# Sheet2.net
KiCad netlist of a schematic drawn in Altium Designer
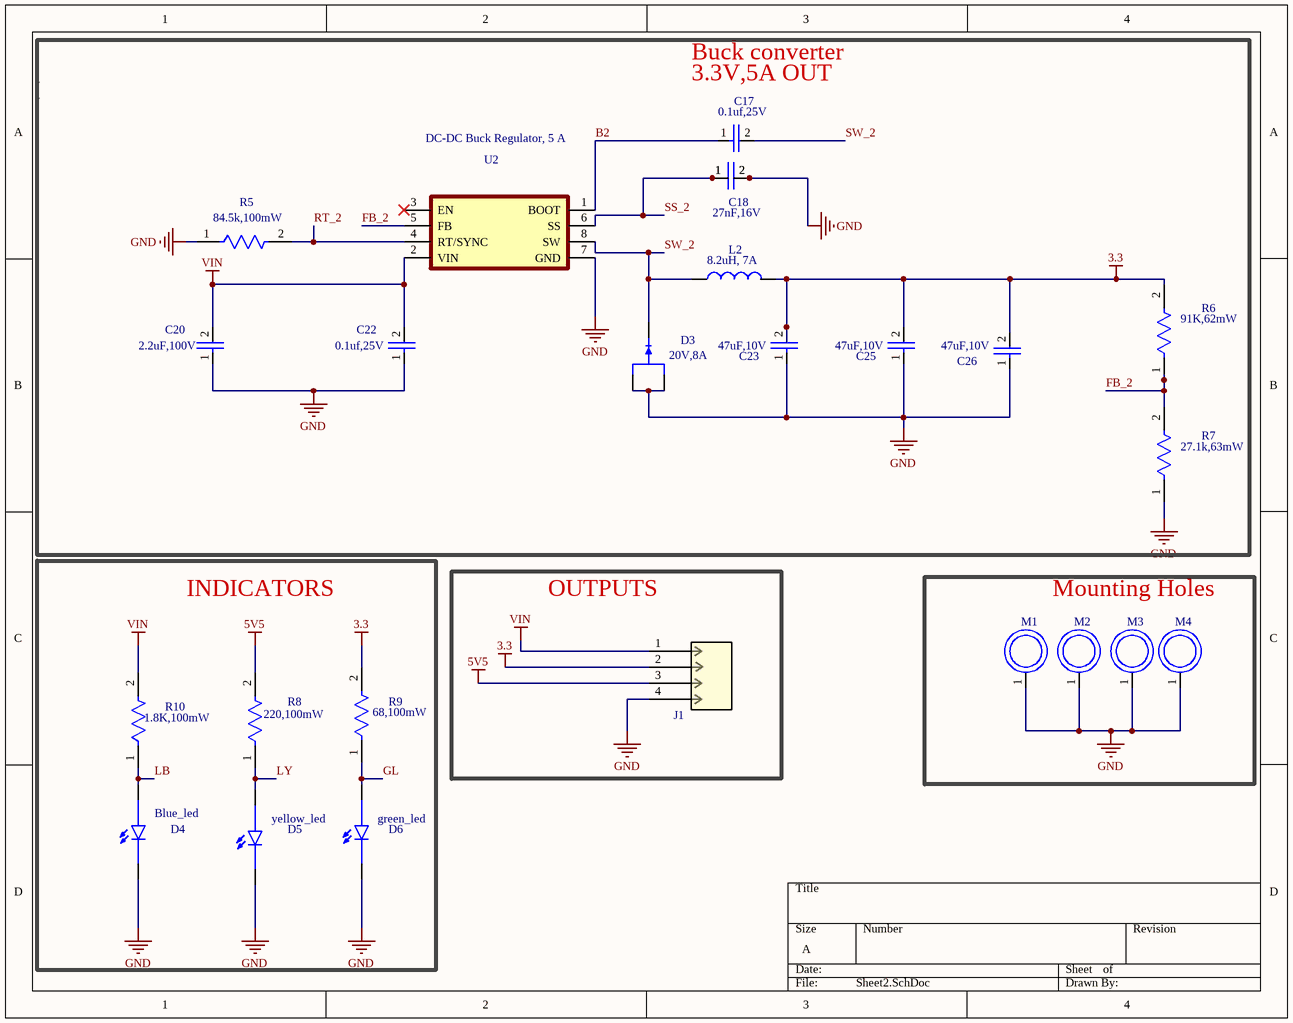
[diagram p0: Sheet2.SchDoc]

(export (version "E")
  (design (tool "Eeschema 10.0.6"))
  (components
    (comp (ref "C17")
      (value "0.1uf,25V")
      (footprint "CC0603KRX7R8BB104")
      (description "25V 100nF X7R ±10% 0603 Ceramic Capacitors ROHS")
      (fields (field (name "MANAFUCTURER PART NUMBER") "CC0603KRX7R8BB104"))
      (libsource (lib "Schlib1") (part "CC0603KRX7R8BB104"))
    )
    (comp (ref "C18")
      (value "27nF,16V")
      (footprint "C0805C273K4HACAUTO")
      (description "16V 27nF X8R ±10% 0805 Ceramic Capacitors ROHS")
      (libsource (lib "Schlib1") (part "C0805C273K4HACAUTO"))
    )
    (comp (ref "C20")
      (value "2.2uF,100V")
      (footprint "CL31A106KBHNNNE")
      (description "100V 2.2uF X7R ±10% 1206 Ceramic Capacitors ROHS")
      (fields (field (name "MANAFUCTURER PART NUMBER") "CL31B225KCHSNNE"))
      (libsource (lib "Schlib1") (part "CL31B225KCHSNNE"))
    )
    (comp (ref "C22")
      (value "0.1uf,25V")
      (footprint "CC0603KRX7R8BB104")
      (description "25V 100nF X7R ±10% 0603 Ceramic Capacitors ROHS")
      (fields (field (name "MANAFUCTURER PART NUMBER") "CC0603KRX7R8BB104"))
      (libsource (lib "Schlib1") (part "CC0603KRX7R8BB104"))
    )
    (comp (ref "C23")
      (value "47uF,10V")
      (footprint "GRM31CR61A476ME15L")
      (description "10V 47uF X5R ±20% 1206 Ceramic Capacitors ROHS")
      (fields (field (name "MANAFUCTURER PART NUMBER") "GRM31CR61A476ME15L"))
      (libsource (lib "Schlib1") (part "GRM31CR61A476ME15L"))
    )
    (comp (ref "C25")
      (value "47uF,10V")
      (footprint "GRM31CR61A476ME15L")
      (description "10V 47uF X5R ±20% 1206 Ceramic Capacitors ROHS")
      (fields (field (name "MANAFUCTURER PART NUMBER") "GRM31CR61A476ME15L"))
      (libsource (lib "Schlib1") (part "GRM31CR61A476ME15L"))
    )
    (comp (ref "C26")
      (value "47uF,10V")
      (footprint "GRM31CR61A476ME15L")
      (description "10V 47uF X5R ±20% 1206 Ceramic Capacitors ROHS")
      (fields (field (name "MANAFUCTURER PART NUMBER") "GRM31CR61A476ME15L"))
      (libsource (lib "Schlib1") (part "GRM31CR61A476ME15L"))
    )
    (comp (ref "D3")
      (value "20V,8A")
      (footprint "SS12P2L-M3/86A")
      (description "20V 560mV@12A 12A TO-277A Single Diodes ROHS")
      (fields (field (name "MANAFUCTURER PART NUMBER") "SS12P2L-M3/86A"))
      (libsource (lib "Schlib1") (part "SS12P2L-M3/86A"))
    )
    (comp (ref "D4")
      (value "Blue_led")
      (footprint "XL-1608UBC-04")
      (description "20mA 3.3V Blue 70mW 0603 LED Indication - Discrete ROHS")
      (fields (field (name "MANAFUCTURER PART NUMBER") "XL-1608UBC-04"))
      (libsource (lib "Schlib1") (part "XL-1608UBC-04"))
    )
    (comp (ref "D5")
      (value "yellow_led")
      (footprint "XL-1608UWC-04")
      (description "20mA 13700K~33000K White 2.7V 70mW 0603 LED Indication - Discrete ROHS")
      (libsource (lib "Schlib1") (part "XL-1608UWC-04"))
    )
    (comp (ref "D6")
      (value "green_led")
      (footprint "LTST-C190GKT")
      (description "63mW 27.1kΩ ±25ppm/℃ Thin Film Resistor ±0.1% 0402 Chip Resistor - Surface Mount ROHS")
      (libsource (lib "Schlib1") (part "LTST-C190GKT"))
    )
    (comp (ref "J1")
      (value "Through Hole,P=2.54mm")
      (footprint "PBC04SAAN")
      (libsource (lib "Schlib1") (part "PBC04SAAN"))
    )
    (comp (ref "L2")
      (value "8.2uH, 7A")
      (footprint "SCIHP1040-8R2M")
      (description "7A 8.2uH ±20% 10A 31mΩ SMD,11.5x10.2mm Fixed Inductors ROHS")
      (fields (field (name "MANAFUCTURER PART NUMBER") "SCIHP1040-8R2M"))
      (libsource (lib "Schlib1") (part "SCIHP1040-8R2M"))
    )
    (comp (ref "M1")
      (value "2..2mm")
      (footprint "mountinh hole")
      (description "mounting hole 2.2m")
      (libsource (lib "Schlib1") (part "mountin_holes"))
    )
    (comp (ref "M2")
      (value "2..2mm")
      (footprint "mountinh hole")
      (description "mounting hole 2.2m")
      (libsource (lib "Schlib1") (part "mountin_holes"))
    )
    (comp (ref "M3")
      (value "2..2mm")
      (footprint "mountinh hole")
      (description "mounting hole 2.2m")
      (libsource (lib "Schlib1") (part "mountin_holes"))
    )
    (comp (ref "M4")
      (value "2..2mm")
      (footprint "mountinh hole")
      (description "mounting hole 2.2m")
      (libsource (lib "Schlib1") (part "mountin_holes"))
    )
    (comp (ref "R5")
      (value "84.5k,100mW")
      (footprint "RC0603FR-0784K5L")
      (description "100mW 84.5kΩ 75V ±100ppm/℃ Thick Film Resistor ±1% 0603 Chip Resistor - Surface Mount ROHS")
      (fields (field (name "MANAFUCTURER PART NUMBER") "RC0603FR-0784K5L"))
      (libsource (lib "Schlib1") (part "RC0603FR-0784K5L"))
    )
    (comp (ref "R6")
      (value "91K,62mW")
      (footprint "RC0402FR-0791KL")
      (description "91kΩ 62.5mW 50V ±100ppm/℃ Thick Film Resistor ±1% 0402 Chip Resistor - Surface Mount ROHS")
      (libsource (lib "Schlib1") (part "RC0402FR-0791KL"))
    )
    (comp (ref "R7")
      (value "27.1k,63mW")
      (footprint "TNPW040227K1BEED")
      (description "63mW 27.1kΩ ±25ppm/℃ Thin Film Resistor ±0.1% 0402 Chip Resistor - Surface Mount ROHS")
      (libsource (lib "Schlib1") (part "TNPW040227K1BEED"))
    )
    (comp (ref "R8")
      (value "220,100mW")
      (footprint "RMCF0603JT220R")
      (description "100mW 220Ω 75V ±200ppm/℃ Thick Film Resistor ±5% 0603 Chip Resistor - Surface Mount ROHS")
      (libsource (lib "Schlib1") (part "RMCF0603JT220R"))
    )
    (comp (ref "R9")
      (value "68,100mW")
      (footprint "RC0603JR-0768RL")
      (description "100mW 68Ω 75V ±100ppm/℃ Thick Film Resistor ±5% 0603 Chip Resistor - Surface Mount ROHS")
      (libsource (lib "Schlib1") (part "RC0603JR-0768RL"))
    )
    (comp (ref "R10")
      (value "1.8K,100mW")
      (footprint "RMCF0603JT1K80")
      (description "100mW 1.8kΩ 75V ±200ppm/℃ Thick Film Resistor ±5% 0603 Chip Resistor - Surface Mount ROHS")
      (libsource (lib "Schlib1") (part "RMCF0603JT1K80"))
    )
    (comp (ref "U2")
      (value "DC-DC Buck Regulator, 5 A")
      (footprint "LMR14050SDDAR")
      (fields (field (name "MANAFUCTURER PART NUMBER") "LMR14050SDDAR"))
      (libsource (lib "Schlib1") (part "LMR14050SDDAR"))
    )
  )
  (nets
    (net (code "1") (name "/B2") (class "Default")
      (node (ref "C17") (pin "1") (pinfunction "1_1") (pintype "passive"))
      (node (ref "U2") (pin "1") (pinfunction "BOOT_1") (pintype "passive"))
    )
    (net (code "2") (name "/FB_2") (class "Default")
      (node (ref "R6") (pin "1") (pinfunction "1_1") (pintype "passive"))
      (node (ref "R7") (pin "2") (pinfunction "2_2") (pintype "passive"))
      (node (ref "U2") (pin "5") (pinfunction "FB_5") (pintype "passive"))
    )
    (net (code "3") (name "/GL") (class "Default")
      (node (ref "D6") (pin "A") (pinfunction "A_A") (pintype "passive"))
      (node (ref "R9") (pin "1") (pinfunction "1_1") (pintype "passive"))
    )
    (net (code "4") (name "/LB") (class "Default")
      (node (ref "D4") (pin "A") (pinfunction "A_A") (pintype "passive"))
      (node (ref "R10") (pin "1") (pinfunction "1_1") (pintype "passive"))
    )
    (net (code "5") (name "/LY") (class "Default")
      (node (ref "D5") (pin "A") (pinfunction "A_A") (pintype "passive"))
      (node (ref "R8") (pin "1") (pinfunction "1_1") (pintype "passive"))
    )
    (net (code "6") (name "/RT_2") (class "Default")
      (node (ref "R5") (pin "2") (pinfunction "2_2") (pintype "passive"))
      (node (ref "U2") (pin "4") (pinfunction "RT/SYNC_4") (pintype "passive"))
    )
    (net (code "7") (name "/SS_2") (class "Default")
      (node (ref "C18") (pin "1") (pinfunction "1_1") (pintype "passive"))
      (node (ref "U2") (pin "6") (pinfunction "SS_6") (pintype "passive"))
    )
    (net (code "8") (name "/SW_2") (class "Default")
      (node (ref "C17") (pin "2") (pinfunction "2_2") (pintype "passive"))
      (node (ref "D3") (pin "3") (pinfunction "K_3") (pintype "passive"))
      (node (ref "L2") (pin "1") (pinfunction "1_1") (pintype "passive"))
      (node (ref "U2") (pin "8") (pinfunction "SW_8") (pintype "passive"))
    )
    (net (code "9") (name "3.3") (class "Default")
      (node (ref "C23") (pin "2") (pinfunction "2_2") (pintype "passive"))
      (node (ref "C25") (pin "2") (pinfunction "2_2") (pintype "passive"))
      (node (ref "C26") (pin "2") (pinfunction "2_2") (pintype "passive"))
      (node (ref "J1") (pin "2") (pinfunction "2_2") (pintype "passive"))
      (node (ref "L2") (pin "2") (pinfunction "2_2") (pintype "passive"))
      (node (ref "R6") (pin "2") (pinfunction "2_2") (pintype "passive"))
      (node (ref "R9") (pin "2") (pinfunction "2_2") (pintype "passive"))
    )
    (net (code "10") (name "5V5") (class "Default")
      (node (ref "J1") (pin "3") (pinfunction "3_3") (pintype "passive"))
      (node (ref "R8") (pin "2") (pinfunction "2_2") (pintype "passive"))
    )
    (net (code "11") (name "GND") (class "Default")
      (node (ref "C18") (pin "2") (pinfunction "2_2") (pintype "passive"))
      (node (ref "C20") (pin "1") (pinfunction "1_1") (pintype "passive"))
      (node (ref "C22") (pin "1") (pinfunction "1_1") (pintype "passive"))
      (node (ref "C23") (pin "1") (pinfunction "1_1") (pintype "passive"))
      (node (ref "C25") (pin "1") (pinfunction "1_1") (pintype "passive"))
      (node (ref "C26") (pin "1") (pinfunction "1_1") (pintype "passive"))
      (node (ref "D3") (pin "1") (pinfunction "A1_1") (pintype "passive"))
      (node (ref "D3") (pin "2") (pinfunction "A2_2") (pintype "passive"))
      (node (ref "D4") (pin "C") (pinfunction "C_C") (pintype "passive"))
      (node (ref "D5") (pin "C") (pinfunction "C_C") (pintype "passive"))
      (node (ref "D6") (pin "C") (pinfunction "C_C") (pintype "passive"))
      (node (ref "J1") (pin "4") (pinfunction "4_4") (pintype "passive"))
      (node (ref "M1") (pin "1") (pinfunction "0_1") (pintype "passive"))
      (node (ref "M2") (pin "1") (pinfunction "0_1") (pintype "passive"))
      (node (ref "M3") (pin "1") (pinfunction "0_1") (pintype "passive"))
      (node (ref "M4") (pin "1") (pinfunction "0_1") (pintype "passive"))
      (node (ref "R5") (pin "1") (pinfunction "1_1") (pintype "passive"))
      (node (ref "R7") (pin "1") (pinfunction "1_1") (pintype "passive"))
      (node (ref "U2") (pin "7") (pinfunction "GND_7") (pintype "passive"))
    )
    (net (code "12") (name "VIN") (class "Default")
      (node (ref "C20") (pin "2") (pinfunction "2_2") (pintype "passive"))
      (node (ref "C22") (pin "2") (pinfunction "2_2") (pintype "passive"))
      (node (ref "J1") (pin "1") (pinfunction "1_1") (pintype "passive"))
      (node (ref "R10") (pin "2") (pinfunction "2_2") (pintype "passive"))
      (node (ref "U2") (pin "2") (pinfunction "VIN_2") (pintype "passive"))
    )
    (net (code "13") (name "unconnected-(U2-EN-Pad3)") (class "Default")
      (node (ref "U2") (pin "3") (pinfunction "EN_3") (pintype "passive+no_connect"))
    )
  )
)
